# 2312_Puissance.net
KiCad netlist of a schematic drawn in Altium Designer
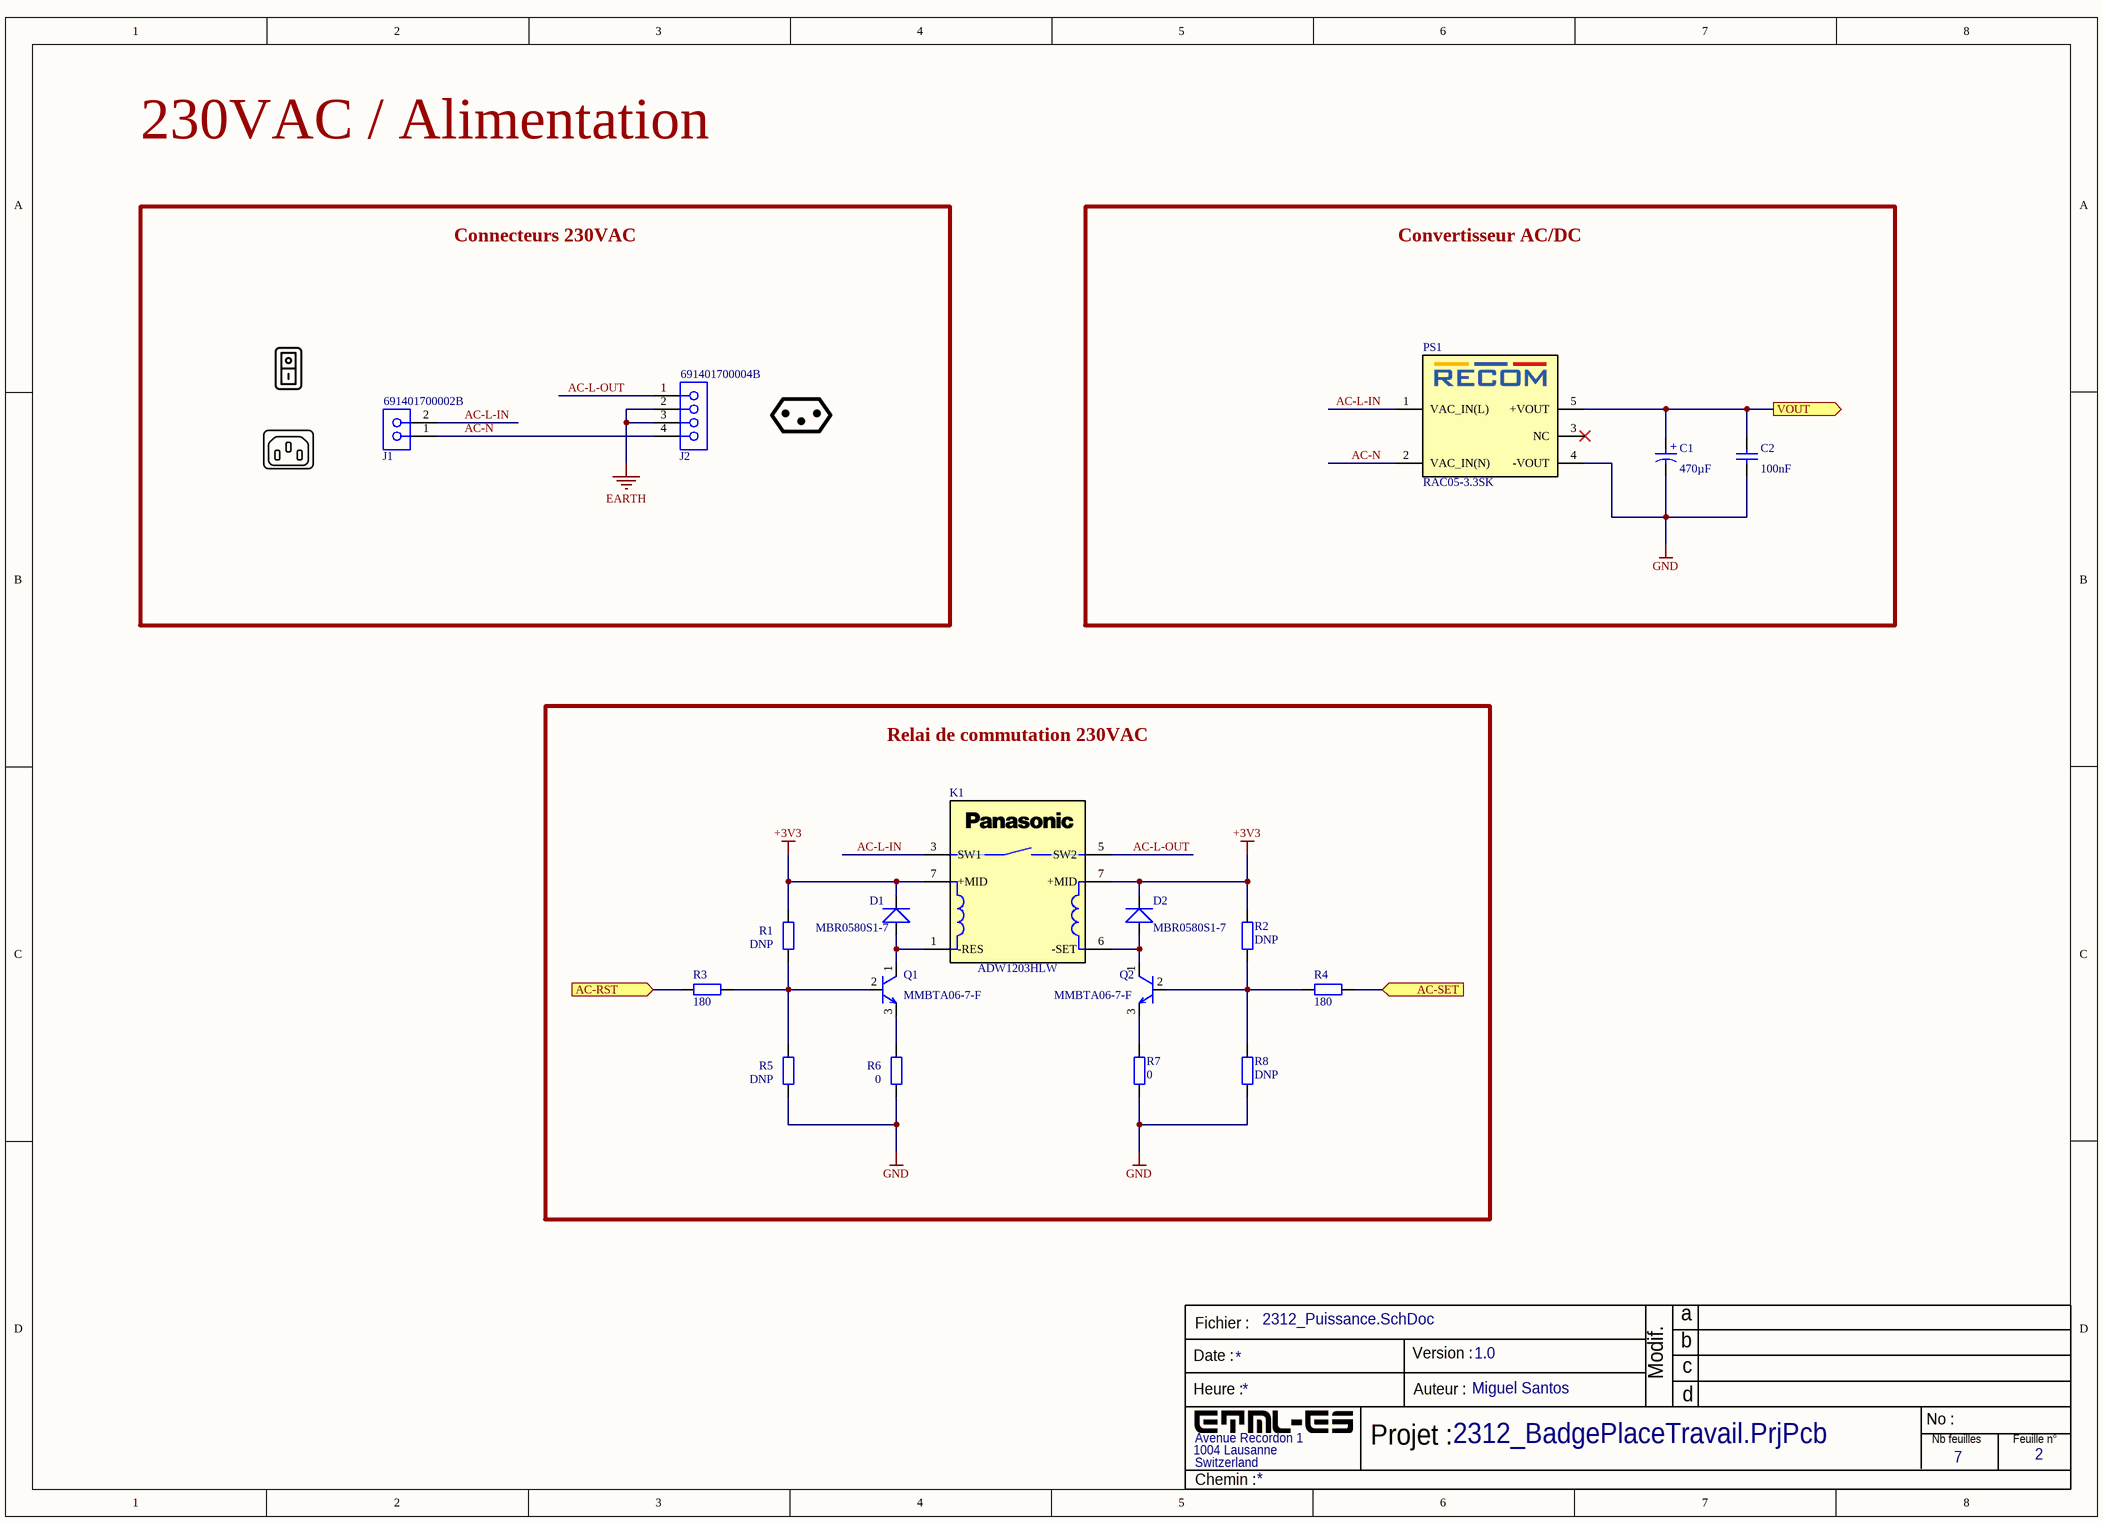
[diagram p0: 2312_Puissance.SchDoc]

(export (version "E")
  (design (tool "Eeschema 10.0.6"))
  (components
    (comp (ref "C1")
      (value "875115150005")
      (footprint "WCAP-PSHP_D8H7.7")
      (description "WCAP-PSHP Aluminum Polymer Capacitor, V-Chip, SMT, D8 x H7.7mm, 470µF, 6.3V")
      (fields (field (name "MANUFACTURER") "Wurth Elektronik") (field (name "CAPACITANCE") "470µF"))
      (libsource (lib "WCAP-PSHP") (part "875115150005"))
    )
    (comp (ref "C2")
      (value "885012207016")
      (footprint "WCAP-CSGP_0805_L2W1.25H0.8_Reflow")
      (description "WCAP-CSGP Multilayer Ceramic Chip Capacitor, General Purpose, size 0805, X7R, 100nF, 10VDC")
      (fields (field (name "MANUFACTURER") "Wurth Elektronik") (field (name "CAPACITANCE") "100nF"))
      (libsource (lib "WCAP-CSGP") (part "885012207016"))
    )
    (comp (ref "D1")
      (value "MBR0580S1-7")
      (footprint "MBR0580S1-7_DIO-M")
      (description "Diode Shottky, 500mA, 80V")
      (libsource (lib "MBR0580S1-7") (part "MBR0580S1-7"))
    )
    (comp (ref "D2")
      (value "MBR0580S1-7")
      (footprint "MBR0580S1-7_DIO-M")
      (description "Diode Shottky, 500mA, 80V")
      (libsource (lib "MBR0580S1-7") (part "MBR0580S1-7"))
    )
    (comp (ref "J1")
      (value "691401700002B")
      (footprint "691401700002B")
      (description "WR-TBL Series 401B Vertical Entry, THT, pitch 5mm, 2p")
      (fields (field (name "MANUFACTURER") "Wurth Elektronik"))
      (libsource (lib "WR-TBL") (part "691401700002B"))
    )
    (comp (ref "J2")
      (value "691401700004B")
      (footprint "691401700004B")
      (description "WR-TBL Series 401B Vertical Entry, THT, pitch 5mm, 4p")
      (fields (field (name "MANUFACTURER") "Wurth Elektronik"))
      (libsource (lib "WR-TBL") (part "691401700004B"))
    )
    (comp (ref "K1")
      (value "ADW1203HLW")
      (footprint "ADW1203HLW")
      (description "RELAY GEN PURPOSE SPST 16A 3V")
      (fields (field (name "MANUFACTURER") "Panasonic Electric Works"))
      (libsource (lib "ADW1203HLW") (part "ADW1203HLW"))
    )
    (comp (ref "PS1")
      (value "RAC05-3.3SK")
      (footprint "CONV_RAC05-3.3SK")
      (description "5W AC/DC-Converter 'POWERLINE' 1x1 4kV reg")
      (fields (field (name "MF") "Recom Power"))
      (libsource (lib "RAC05-3.3SK") (part "RAC05-3.3SK"))
    )
    (comp (ref "Q1")
      (value "MMBTA06-7-F")
      (footprint "SOT91P240X120-3N")
      (description "Bipolar (BJT) Transistor NPN 80V 500mA 100MHz 225mW Surface Mount SOT-23-3 (TO-236)")
      (libsource (lib "MMBTA06-7-F") (part "MMBTA06LT3G"))
    )
    (comp (ref "Q2")
      (value "MMBTA06-7-F")
      (footprint "SOT91P240X120-3N")
      (description "Bipolar (BJT) Transistor NPN 80V 500mA 100MHz 225mW Surface Mount SOT-23-3 (TO-236)")
      (libsource (lib "MMBTA06-7-F") (part "MMBTA06LT3G"))
    )
    (comp (ref "R1")
      (value "RES-0805")
      (footprint "2312-RES-0805")
      (description "SMD Resistor 0805, 1.4kΩ")
      (fields (field (name "RESISTANCE") "DNP"))
      (libsource (lib "2312-MS-0805") (part "RES-0805"))
    )
    (comp (ref "R2")
      (value "RES-0805")
      (footprint "2312-RES-0805")
      (description "SMD Resistor 0805, DNP")
      (fields (field (name "RESISTANCE") "DNP"))
      (libsource (lib "2312-MS-0805") (part "RES-0805"))
    )
    (comp (ref "R3")
      (value "RES-0805")
      (footprint "2312-RES-0805")
      (description "SMD Resistor 0805, 140Ω")
      (fields (field (name "RESISTANCE") "180"))
      (libsource (lib "2312-MS-0805") (part "RES-0805"))
    )
    (comp (ref "R4")
      (value "RES-0805")
      (footprint "2312-RES-0805")
      (description "SMD Resistor 0805, 140Ω")
      (fields (field (name "RESISTANCE") "180"))
      (libsource (lib "2312-MS-0805") (part "RES-0805"))
    )
    (comp (ref "R5")
      (value "RES-0805")
      (footprint "2312-RES-0805")
      (description "SMD Resistor 0805, DNP")
      (fields (field (name "RESISTANCE") "DNP"))
      (libsource (lib "2312-MS-0805") (part "RES-0805"))
    )
    (comp (ref "R6")
      (value "RES-0805")
      (footprint "2312-RES-0805")
      (description "SMD Resistor 0805, 2Ω")
      (fields (field (name "RESISTANCE") "0"))
      (libsource (lib "2312-MS-0805") (part "RES-0805"))
    )
    (comp (ref "R7")
      (value "RES-0805")
      (footprint "2312-RES-0805")
      (description "SMD Resistor 0805, 2Ω")
      (fields (field (name "RESISTANCE") "0"))
      (libsource (lib "2312-MS-0805") (part "RES-0805"))
    )
    (comp (ref "R8")
      (value "RES-0805")
      (footprint "2312-RES-0805")
      (description "SMD Resistor 0805, 1.4kΩ")
      (fields (field (name "RESISTANCE") "DNP"))
      (libsource (lib "2312-MS-0805") (part "RES-0805"))
    )
  )
  (nets
    (net (code "1") (name "+3V3") (class "Default")
      (node (ref "D1") (pin "2") (pinfunction "2_2") (pintype "passive"))
      (node (ref "D2") (pin "2") (pinfunction "2_2") (pintype "passive"))
      (node (ref "K1") (pin "7") (pinfunction "+MID_7") (pintype "passive"))
      (node (ref "R1") (pin "2") (pinfunction "2_2") (pintype "passive"))
      (node (ref "R2") (pin "2") (pinfunction "2_2") (pintype "passive"))
    )
    (net (code "2") (name "/AC-L-IN") (class "Default")
      (node (ref "J1") (pin "2") (pinfunction "2_2") (pintype "passive"))
      (node (ref "K1") (pin "3") (pinfunction "SW1_3") (pintype "passive"))
      (node (ref "PS1") (pin "1") (pinfunction "VAC_IN(L)_1") (pintype "passive"))
    )
    (net (code "3") (name "/AC-L-OUT") (class "Default")
      (node (ref "J2") (pin "1") (pinfunction "1_1") (pintype "passive"))
      (node (ref "K1") (pin "5") (pinfunction "SW2_5") (pintype "passive"))
    )
    (net (code "4") (name "/AC-N") (class "Default")
      (node (ref "J1") (pin "1") (pinfunction "1_1") (pintype "passive"))
      (node (ref "J2") (pin "4") (pinfunction "4_4") (pintype "passive"))
      (node (ref "PS1") (pin "2") (pinfunction "VAC_IN(N)_2") (pintype "passive"))
    )
    (net (code "5") (name "/AC-RST") (class "Default")
      (node (ref "R3") (pin "2") (pinfunction "2_2") (pintype "passive"))
    )
    (net (code "6") (name "/AC-SET") (class "Default")
      (node (ref "R4") (pin "1") (pinfunction "1_1") (pintype "passive"))
    )
    (net (code "7") (name "/VOUT") (class "Default")
      (node (ref "C1") (pin "1") (pinfunction "P_1") (pintype "passive"))
      (node (ref "C2") (pin "2") (pinfunction "2_2") (pintype "passive"))
      (node (ref "PS1") (pin "5") (pinfunction "+VOUT_5") (pintype "passive"))
    )
    (net (code "8") (name "EARTH") (class "Default")
      (node (ref "J2") (pin "2") (pinfunction "2_2") (pintype "passive"))
      (node (ref "J2") (pin "3") (pinfunction "3_3") (pintype "passive"))
    )
    (net (code "9") (name "GND") (class "Default")
      (node (ref "C1") (pin "2") (pinfunction "N_2") (pintype "passive"))
      (node (ref "C2") (pin "1") (pinfunction "1_1") (pintype "passive"))
      (node (ref "PS1") (pin "4") (pinfunction "-VOUT_4") (pintype "passive"))
      (node (ref "R5") (pin "1") (pinfunction "1_1") (pintype "passive"))
      (node (ref "R6") (pin "1") (pinfunction "1_1") (pintype "passive"))
      (node (ref "R7") (pin "1") (pinfunction "1_1") (pintype "passive"))
      (node (ref "R8") (pin "1") (pinfunction "1_1") (pintype "passive"))
    )
    (net (code "10") (name "Net-(K1--RES)") (class "Default")
      (node (ref "D1") (pin "1") (pinfunction "1_1") (pintype "passive"))
      (node (ref "K1") (pin "1") (pinfunction "-RES_1") (pintype "passive"))
      (node (ref "Q1") (pin "1") (pinfunction "COLLECTOR_1") (pintype "passive"))
    )
    (net (code "11") (name "Net-(K1--SET)") (class "Default")
      (node (ref "D2") (pin "1") (pinfunction "1_1") (pintype "passive"))
      (node (ref "K1") (pin "6") (pinfunction "-SET_6") (pintype "passive"))
      (node (ref "Q2") (pin "1") (pinfunction "COLLECTOR_1") (pintype "passive"))
    )
    (net (code "12") (name "Net-(Q1-BASE)") (class "Default")
      (node (ref "Q1") (pin "2") (pinfunction "BASE_2") (pintype "passive"))
      (node (ref "R1") (pin "1") (pinfunction "1_1") (pintype "passive"))
      (node (ref "R3") (pin "1") (pinfunction "1_1") (pintype "passive"))
      (node (ref "R5") (pin "2") (pinfunction "2_2") (pintype "passive"))
    )
    (net (code "13") (name "Net-(Q1-EMITTER)") (class "Default")
      (node (ref "Q1") (pin "3") (pinfunction "EMITTER_3") (pintype "passive"))
      (node (ref "R6") (pin "2") (pinfunction "2_2") (pintype "passive"))
    )
    (net (code "14") (name "Net-(Q2-BASE)") (class "Default")
      (node (ref "Q2") (pin "2") (pinfunction "BASE_2") (pintype "passive"))
      (node (ref "R2") (pin "1") (pinfunction "1_1") (pintype "passive"))
      (node (ref "R4") (pin "2") (pinfunction "2_2") (pintype "passive"))
      (node (ref "R8") (pin "2") (pinfunction "2_2") (pintype "passive"))
    )
    (net (code "15") (name "Net-(Q2-EMITTER)") (class "Default")
      (node (ref "Q2") (pin "3") (pinfunction "EMITTER_3") (pintype "passive"))
      (node (ref "R7") (pin "2") (pinfunction "2_2") (pintype "passive"))
    )
    (net (code "16") (name "unconnected-(PS1-NC-Pad3)") (class "Default")
      (node (ref "PS1") (pin "3") (pinfunction "NC_3") (pintype "passive+no_connect"))
    )
  )
)
